# ETH_1G_RGMII_RTL8211F.net
KiCad netlist of a schematic drawn in Altium Designer
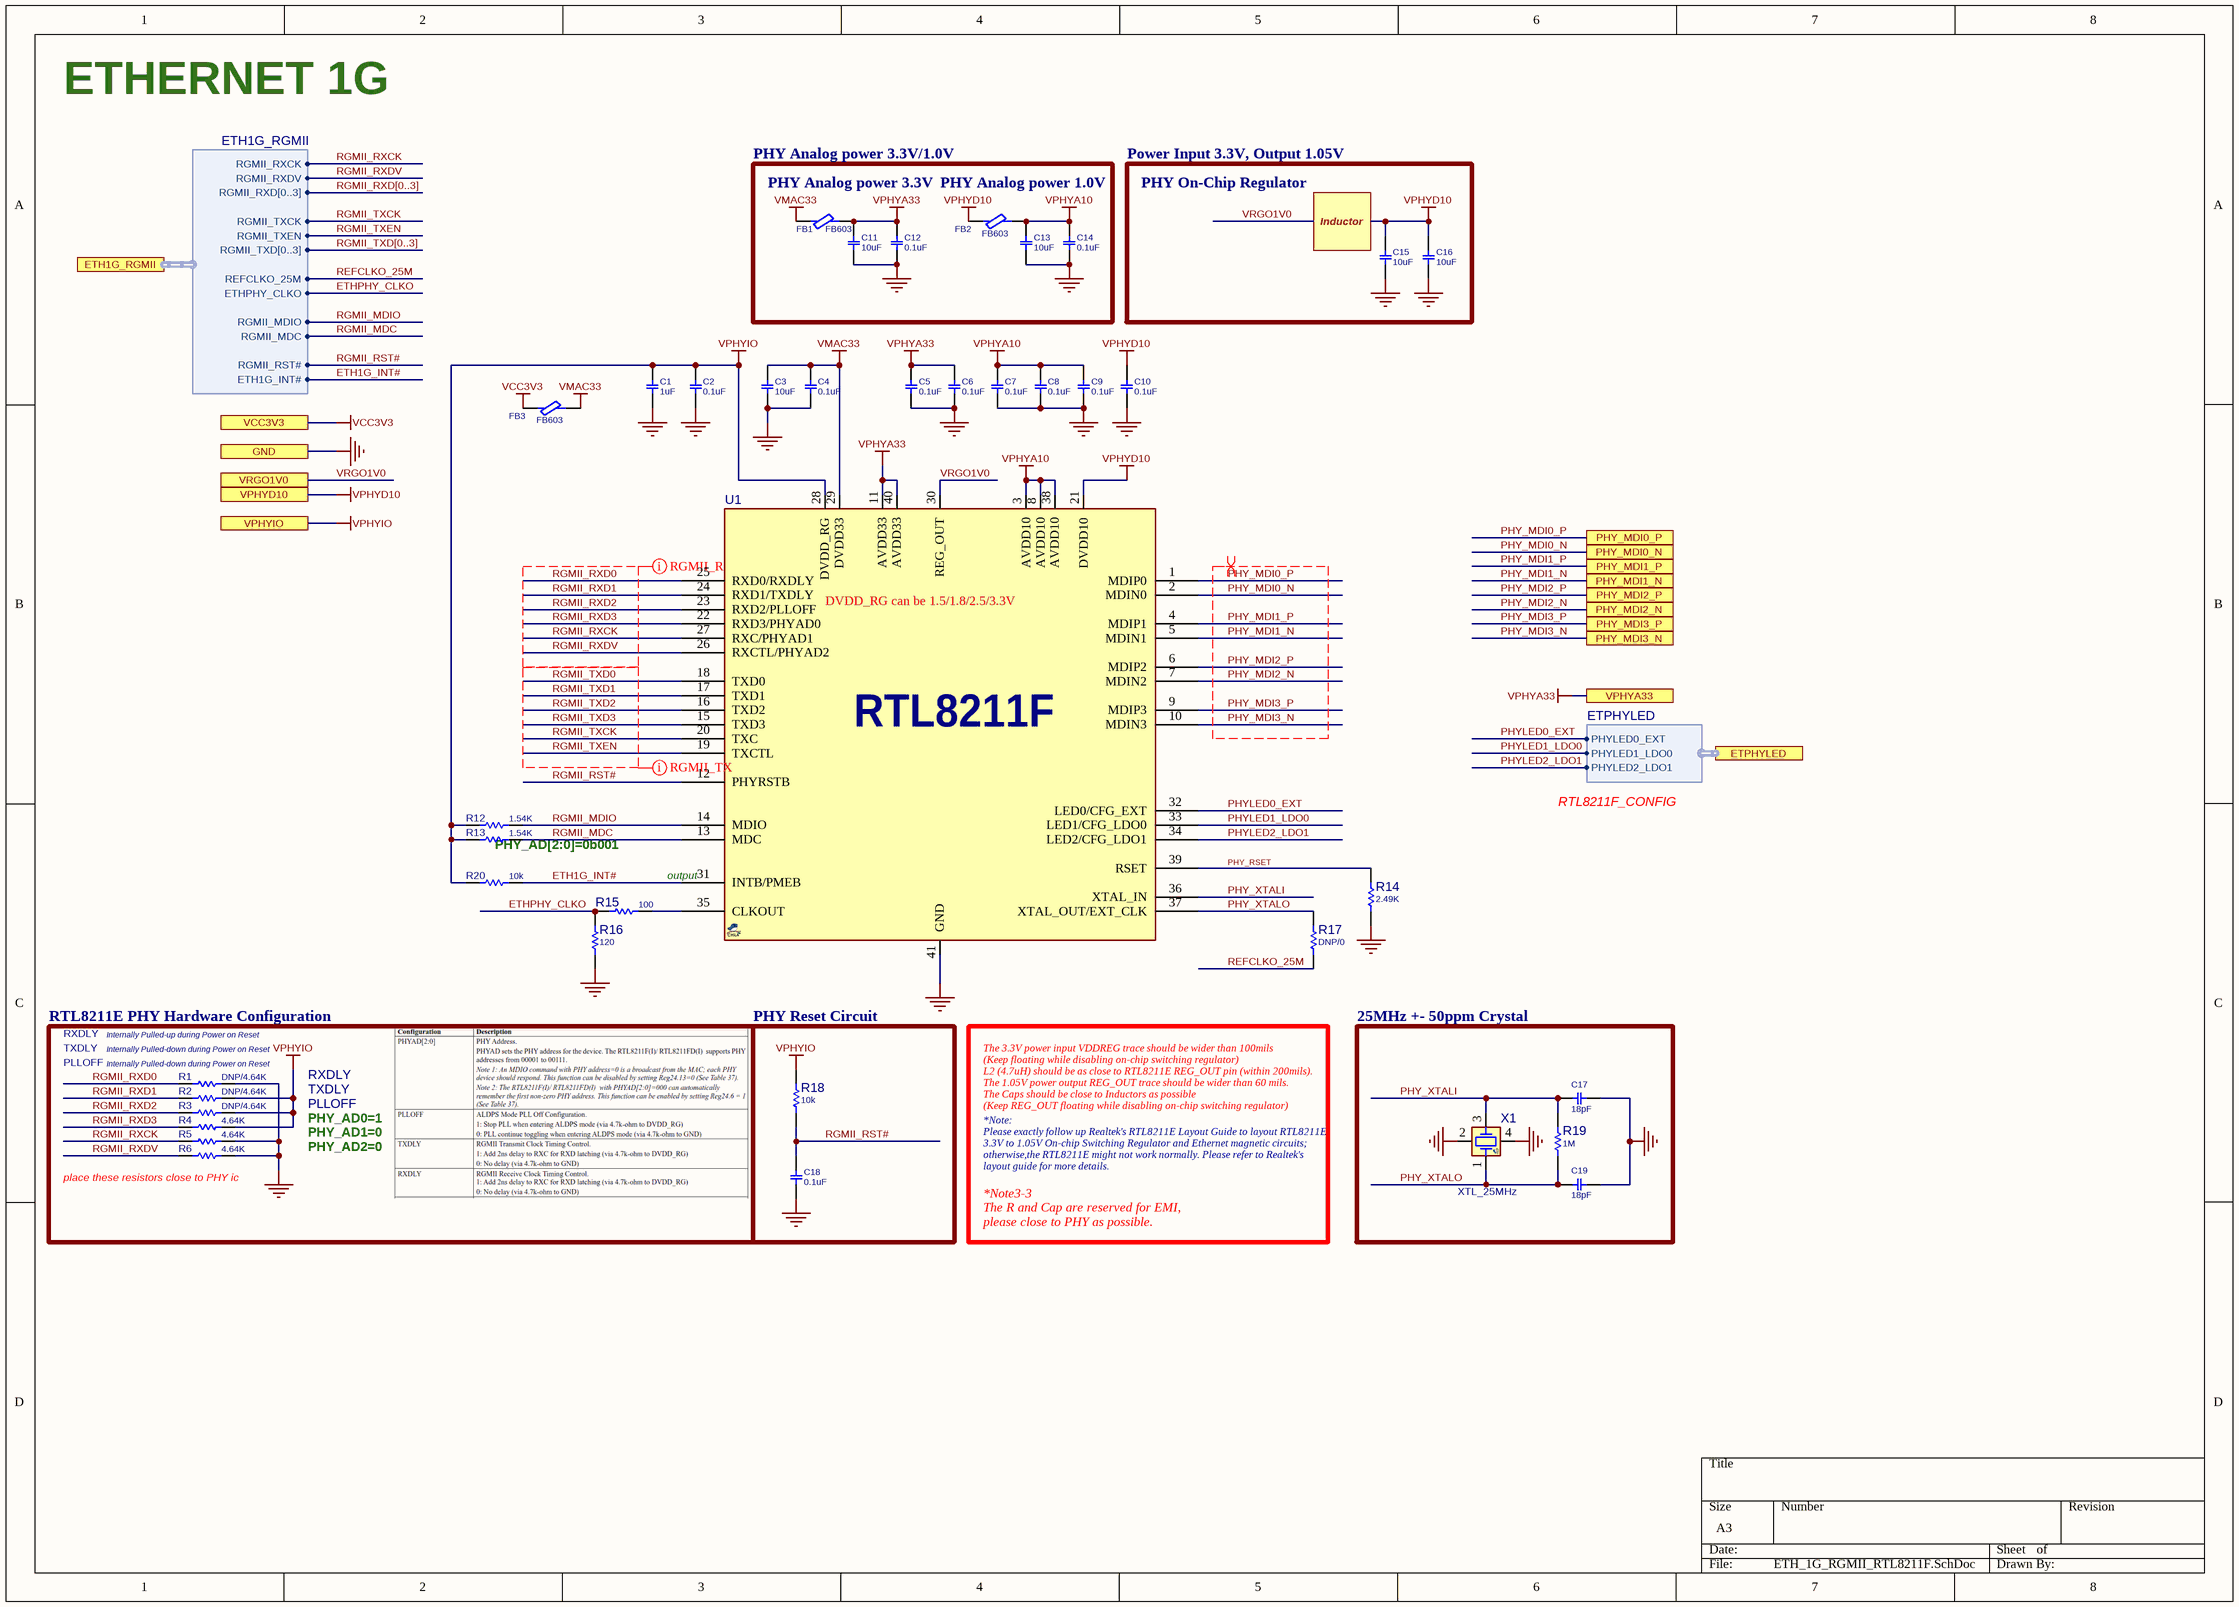
[diagram p0: ETH_1G_RGMII_RTL8211F.SchDoc]

(export (version "E")
  (design (tool "Eeschema 10.0.6"))
  (components
    (comp (ref "C1")
      (value "1uF")
      (footprint "C0402")
      (description "CAP, MLCC")
      (fields (field (name "MANF_P#") "CL05A105KO5NNND") (field (name "MANF") "Samsung"))
      (libsource (lib "passive_smd") (part "CAP_SMD_MLCC"))
    )
    (comp (ref "C2")
      (value "0.1uF")
      (footprint "C0402")
      (description "CAP, MLCC")
      (fields (field (name "MANF_P#") "GRM155R61E104") (field (name "MANF") "Murata"))
      (libsource (lib "mlcc_smd_passive") (part "CAP_SMD_MLCC_100n50T"))
    )
    (comp (ref "C3")
      (value "10uF")
      (footprint "C0402")
      (description "CAP, MLCC")
      (fields (field (name "MANF_P#") "CL05A106MP5NUNC") (field (name "MANF") "Samsung"))
      (libsource (lib "mlcc_smd_passive") (part "CAP_SMD_MLCC_100n50T"))
    )
    (comp (ref "C4")
      (value "0.1uF")
      (footprint "C0402")
      (description "CAP, MLCC")
      (fields (field (name "MANF_P#") "GRM155R61E104") (field (name "MANF") "Murata"))
      (libsource (lib "mlcc_smd_passive") (part "CAP_SMD_MLCC_100n50T"))
    )
    (comp (ref "C5")
      (value "0.1uF")
      (footprint "C0402")
      (description "CAP, MLCC")
      (fields (field (name "MANF_P#") "GRM155R61E104") (field (name "MANF") "Murata"))
      (libsource (lib "mlcc_smd_passive") (part "CAP_SMD_MLCC_100n50T"))
    )
    (comp (ref "C6")
      (value "0.1uF")
      (footprint "C0402")
      (description "CAP, MLCC")
      (fields (field (name "MANF_P#") "GRM155R61E104") (field (name "MANF") "Murata"))
      (libsource (lib "mlcc_smd_passive") (part "CAP_SMD_MLCC_100n50T"))
    )
    (comp (ref "C7")
      (value "0.1uF")
      (footprint "C0402")
      (description "CAP, MLCC")
      (fields (field (name "MANF_P#") "GRM155R61E104") (field (name "MANF") "Murata"))
      (libsource (lib "mlcc_smd_passive") (part "CAP_SMD_MLCC_100n50T"))
    )
    (comp (ref "C8")
      (value "0.1uF")
      (footprint "C0402")
      (description "CAP, MLCC")
      (fields (field (name "MANF_P#") "GRM155R61E104") (field (name "MANF") "Murata"))
      (libsource (lib "mlcc_smd_passive") (part "CAP_SMD_MLCC_100n50T"))
    )
    (comp (ref "C9")
      (value "0.1uF")
      (footprint "C0402")
      (description "CAP, MLCC")
      (fields (field (name "MANF_P#") "GRM155R61E104") (field (name "MANF") "Murata"))
      (libsource (lib "mlcc_smd_passive") (part "CAP_SMD_MLCC_100n50T"))
    )
    (comp (ref "C10")
      (value "0.1uF")
      (footprint "C0402")
      (description "CAP, MLCC")
      (fields (field (name "MANF_P#") "GRM155R61E104") (field (name "MANF") "Murata"))
      (libsource (lib "mlcc_smd_passive") (part "CAP_SMD_MLCC_100n50T"))
    )
    (comp (ref "C11")
      (value "10uF")
      (footprint "C0402")
      (description "CAP, MLCC")
      (fields (field (name "MANF_P#") "CL05A106MP5NUNC") (field (name "MANF") "Samsung"))
      (libsource (lib "mlcc_smd_passive") (part "CAP_SMD_MLCC_100n50T"))
    )
    (comp (ref "C12")
      (value "0.1uF")
      (footprint "C0402")
      (description "CAP, MLCC")
      (fields (field (name "MANF_P#") "GRM155R61E104") (field (name "MANF") "Murata"))
      (libsource (lib "mlcc_smd_passive") (part "CAP_SMD_MLCC_100n50T"))
    )
    (comp (ref "C13")
      (value "10uF")
      (footprint "C0402")
      (description "CAP, MLCC")
      (fields (field (name "MANF_P#") "CL05A106MP5NUNC") (field (name "MANF") "Samsung"))
      (libsource (lib "mlcc_smd_passive") (part "CAP_SMD_MLCC_100n50T"))
    )
    (comp (ref "C14")
      (value "0.1uF")
      (footprint "C0402")
      (description "CAP, MLCC")
      (fields (field (name "MANF_P#") "GRM155R61E104") (field (name "MANF") "Murata"))
      (libsource (lib "mlcc_smd_passive") (part "CAP_SMD_MLCC_100n50T"))
    )
    (comp (ref "C15")
      (value "10uF")
      (footprint "C0402")
      (description "CAP, MLCC")
      (fields (field (name "MANF_P#") "CL05A106MP5NUNC") (field (name "MANF") "Samsung"))
      (libsource (lib "mlcc_smd_passive") (part "CAP_SMD_MLCC_100n50T"))
    )
    (comp (ref "C16")
      (value "10uF")
      (footprint "C0402")
      (description "CAP, MLCC")
      (fields (field (name "MANF_P#") "CL05A106MP5NUNC") (field (name "MANF") "Samsung"))
      (libsource (lib "mlcc_smd_passive") (part "CAP_SMD_MLCC_100n50T"))
    )
    (comp (ref "C17")
      (value "18pF")
      (footprint "C0402")
      (description "CAP, MLCC")
      (fields (field (name "MANF_P#") "CC0402JRNPO9BN180") (field (name "MANF") "Yageo"))
      (libsource (lib "mlcc_smd_passive") (part "CAP_SMD_MLCC_100n50T"))
    )
    (comp (ref "C18")
      (value "0.1uF")
      (footprint "C0402")
      (description "CAP, MLCC")
      (fields (field (name "MANF_P#") "GRM155R61E104") (field (name "MANF") "Murata"))
      (libsource (lib "mlcc_smd_passive") (part "CAP_SMD_MLCC_100n50T"))
    )
    (comp (ref "C19")
      (value "18pF")
      (footprint "C0402")
      (description "CAP, MLCC")
      (fields (field (name "MANF_P#") "CC0402JRNPO9BN180") (field (name "MANF") "Yageo"))
      (libsource (lib "mlcc_smd_passive") (part "CAP_SMD_MLCC_100n50T"))
    )
    (comp (ref "FB1")
      (value "FB603")
      (footprint "L0603")
      (description "FERRITE_Bead, 0603, 0.8A, 300mOhm, 1000@100MHz")
      (fields (field (name "MANF") "MURATA") (field (name "MANF_P#") "BLM18KG601SN1D"))
      (libsource (lib "emi_filter") (part "FBEAD_SMD_MPZ1608S102"))
    )
    (comp (ref "FB2")
      (value "FB603")
      (footprint "L0603")
      (description "FERRITE_Bead, 0603, 0.8A, 300mOhm, 1000@100MHz")
      (fields (field (name "MANF") "MURATA") (field (name "MANF_P#") "BLM18KG601SN1D"))
      (libsource (lib "emi_filter") (part "FBEAD_SMD_MPZ1608S102"))
    )
    (comp (ref "FB3")
      (value "FB603")
      (footprint "L0603")
      (description "FERRITE_Bead, 0603, 0.8A, 300mOhm, 1000@100MHz")
      (fields (field (name "MANF") "MURATA") (field (name "MANF_P#") "BLM18KG601SN1D"))
      (libsource (lib "emi_filter") (part "FBEAD_SMD_MPZ1608S102"))
    )
    (comp (ref "R1")
      (value "DNP/4.64K")
      (footprint "R0402")
      (description "RESISTOR, SMD")
      (libsource (lib "passive_res_smd") (part "RES_SMD_10K_0402"))
    )
    (comp (ref "R2")
      (value "DNP/4.64K")
      (footprint "R0402")
      (description "RESISTOR, SMD")
      (libsource (lib "passive_res_smd") (part "RES_SMD_10K_0402"))
    )
    (comp (ref "R3")
      (value "DNP/4.64K")
      (footprint "R0402")
      (description "RESISTOR, SMD")
      (libsource (lib "passive_res_smd") (part "RES_SMD_10K_0402"))
    )
    (comp (ref "R4")
      (value "4.64K")
      (footprint "R0402")
      (description "RESISTOR, SMD")
      (libsource (lib "passive_res_smd") (part "RES_SMD_10K_0402"))
    )
    (comp (ref "R5")
      (value "4.64K")
      (footprint "R0402")
      (description "RESISTOR, SMD")
      (libsource (lib "passive_res_smd") (part "RES_SMD_10K_0402"))
    )
    (comp (ref "R6")
      (value "4.64K")
      (footprint "R0402")
      (description "RESISTOR, SMD")
      (libsource (lib "passive_res_smd") (part "RES_SMD_10K_0402"))
    )
    (comp (ref "R12")
      (value "1.54K")
      (footprint "R0402")
      (description "RESISTOR, SMD")
      (libsource (lib "passive_res_smd") (part "RES_SMD_10K_0402"))
    )
    (comp (ref "R13")
      (value "1.54K")
      (footprint "R0402")
      (description "RESISTOR, SMD")
      (libsource (lib "passive_res_smd") (part "RES_SMD_10K_0402"))
    )
    (comp (ref "R14")
      (value "2.49K")
      (footprint "R0402")
      (description "RESISTOR, SMD")
      (libsource (lib "passive_res_smd") (part "RES_SMD_10K_0402"))
    )
    (comp (ref "R15")
      (value "100")
      (footprint "R0402")
      (description "RESISTOR, SMD")
      (libsource (lib "passive_res_smd") (part "RES_SMD_10K_0402"))
    )
    (comp (ref "R16")
      (value "120")
      (footprint "R0402")
      (description "RESISTOR, SMD")
      (libsource (lib "passive_res_smd") (part "RES_SMD_10K_0402"))
    )
    (comp (ref "R17")
      (value "DNP/0")
      (footprint "R0402")
      (description "RESISTOR, SMD")
      (libsource (lib "passive_res_smd") (part "RES_SMD_10K_0402"))
    )
    (comp (ref "R18")
      (value "10k")
      (footprint "R0402")
      (description "RESISTOR, SMD")
      (libsource (lib "passive_res_smd") (part "RES_SMD_10K_0402"))
    )
    (comp (ref "R19")
      (value "1M")
      (footprint "R0402")
      (description "RESISTOR, SMD")
      (libsource (lib "passive_res_smd") (part "RES_SMD_10K_0402"))
    )
    (comp (ref "R20")
      (value "10k")
      (footprint "R0402")
      (description "RESISTOR, SMD")
      (libsource (lib "passive_res_smd") (part "RES_SMD_10K_0402"))
    )
    (comp (ref "U1")
      (value "RTL8211F")
      (footprint "QFN40_40T")
      (description "Ethernet Transceiver, 10/100/1000, RGMII")
      (fields (field (name "MANF_P#") "RTL8211FI-CG") (field (name "MANF") "Realtek"))
      (libsource (lib "ethernet") (part "RTL8211F_QFN40"))
    )
    (comp (ref "X1")
      (value "XTL_25MHz")
      (footprint "XTL_4_2016")
      (description "CRYSTAL 25.00 MHZ 6pF, 10PPM")
      (fields (field (name "MANF") "Murata") (field (name "MANF_P#") "XRCGB25M000F1H00R0"))
      (libsource (lib "crystal") (part "XTL_4_25MHz_3225"))
    )
  )
  (nets
    (net (code "3") (name "/ETH1G_INT#") (class "Default")
      (node (ref "R20") (pin "2") (pinfunction "2_2") (pintype "passive"))
      (node (ref "U1") (pin "31") (pinfunction "INTB/PMEB_31") (pintype "passive"))
    )
    (net (code "4") (name "/ETHPHY_CLKO") (class "Default")
      (node (ref "R15") (pin "1") (pinfunction "1_1") (pintype "passive"))
      (node (ref "R16") (pin "2") (pinfunction "2_2") (pintype "passive"))
    )
    (net (code "5") (name "/PHYLED0_EXT") (class "Default")
      (node (ref "U1") (pin "32") (pinfunction "LED0/CFG_EXT_32") (pintype "passive"))
    )
    (net (code "6") (name "/PHYLED1_LDO0") (class "Default")
      (node (ref "U1") (pin "33") (pinfunction "LED1/CFG_LDO0_33") (pintype "passive"))
    )
    (net (code "7") (name "/PHYLED2_LDO1") (class "Default")
      (node (ref "U1") (pin "34") (pinfunction "LED2/CFG_LDO1_34") (pintype "passive"))
    )
    (net (code "8") (name "/PHY_MDI0_N") (class "Default")
      (node (ref "U1") (pin "2") (pinfunction "MDIN0_2") (pintype "passive"))
    )
    (net (code "9") (name "/PHY_MDI0_P") (class "Default")
      (node (ref "U1") (pin "1") (pinfunction "MDIP0_1") (pintype "passive"))
    )
    (net (code "10") (name "/PHY_MDI1_N") (class "Default")
      (node (ref "U1") (pin "5") (pinfunction "MDIN1_5") (pintype "passive"))
    )
    (net (code "11") (name "/PHY_MDI1_P") (class "Default")
      (node (ref "U1") (pin "4") (pinfunction "MDIP1_4") (pintype "passive"))
    )
    (net (code "12") (name "/PHY_MDI2_N") (class "Default")
      (node (ref "U1") (pin "7") (pinfunction "MDIN2_7") (pintype "passive"))
    )
    (net (code "13") (name "/PHY_MDI2_P") (class "Default")
      (node (ref "U1") (pin "6") (pinfunction "MDIP2_6") (pintype "passive"))
    )
    (net (code "14") (name "/PHY_MDI3_N") (class "Default")
      (node (ref "U1") (pin "10") (pinfunction "MDIN3_10") (pintype "passive"))
    )
    (net (code "15") (name "/PHY_MDI3_P") (class "Default")
      (node (ref "U1") (pin "9") (pinfunction "MDIP3_9") (pintype "passive"))
    )
    (net (code "16") (name "/PHY_RSET") (class "Default")
      (node (ref "R14") (pin "2") (pinfunction "2_2") (pintype "passive"))
      (node (ref "U1") (pin "39") (pinfunction "RSET_39") (pintype "passive"))
    )
    (net (code "17") (name "/PHY_XTALI") (class "Default")
      (node (ref "C17") (pin "1") (pinfunction "1_1") (pintype "passive"))
      (node (ref "R19") (pin "2") (pinfunction "2_2") (pintype "passive"))
      (node (ref "U1") (pin "36") (pinfunction "XTAL_IN_36") (pintype "passive"))
      (node (ref "X1") (pin "3") (pinfunction "XB_3") (pintype "passive"))
    )
    (net (code "18") (name "/PHY_XTALO") (class "Default")
      (node (ref "C19") (pin "1") (pinfunction "1_1") (pintype "passive"))
      (node (ref "R17") (pin "2") (pinfunction "2_2") (pintype "passive"))
      (node (ref "R19") (pin "1") (pinfunction "1_1") (pintype "passive"))
      (node (ref "U1") (pin "37") (pinfunction "XTAL_OUT/EXT_CLK_37") (pintype "passive"))
      (node (ref "X1") (pin "1") (pinfunction "XA_1") (pintype "passive"))
    )
    (net (code "19") (name "/REFCLKO_25M") (class "Default")
      (node (ref "R17") (pin "1") (pinfunction "1_1") (pintype "passive"))
    )
    (net (code "20") (name "/RGMII_MDC") (class "Default")
      (node (ref "R13") (pin "2") (pinfunction "2_2") (pintype "passive"))
      (node (ref "U1") (pin "13") (pinfunction "MDC_13") (pintype "passive"))
    )
    (net (code "21") (name "/RGMII_MDIO") (class "Default")
      (node (ref "R12") (pin "2") (pinfunction "2_2") (pintype "passive"))
      (node (ref "U1") (pin "14") (pinfunction "MDIO_14") (pintype "passive"))
    )
    (net (code "22") (name "/RGMII_RST#") (class "Default")
      (node (ref "C18") (pin "2") (pinfunction "2_2") (pintype "passive"))
      (node (ref "R18") (pin "2") (pinfunction "2_2") (pintype "passive"))
      (node (ref "U1") (pin "12") (pinfunction "PHYRSTB_12") (pintype "passive"))
    )
    (net (code "23") (name "/RGMII_RXCK") (class "Default")
      (node (ref "R5") (pin "1") (pinfunction "1_1") (pintype "passive"))
      (node (ref "U1") (pin "27") (pinfunction "RXC/PHYAD1_27") (pintype "passive"))
    )
    (net (code "24") (name "/RGMII_RXD0") (class "Default")
      (node (ref "R1") (pin "1") (pinfunction "1_1") (pintype "passive"))
      (node (ref "U1") (pin "25") (pinfunction "RXD0/RXDLY_25") (pintype "passive"))
    )
    (net (code "25") (name "/RGMII_RXD1") (class "Default")
      (node (ref "R2") (pin "1") (pinfunction "1_1") (pintype "passive"))
      (node (ref "U1") (pin "24") (pinfunction "RXD1/TXDLY_24") (pintype "passive"))
    )
    (net (code "26") (name "/RGMII_RXD2") (class "Default")
      (node (ref "R3") (pin "1") (pinfunction "1_1") (pintype "passive"))
      (node (ref "U1") (pin "23") (pinfunction "RXD2/PLLOFF_23") (pintype "passive"))
    )
    (net (code "27") (name "/RGMII_RXD3") (class "Default")
      (node (ref "R4") (pin "1") (pinfunction "1_1") (pintype "passive"))
      (node (ref "U1") (pin "22") (pinfunction "RXD3/PHYAD0_22") (pintype "passive"))
    )
    (net (code "28") (name "/RGMII_RXDV") (class "Default")
      (node (ref "R6") (pin "1") (pinfunction "1_1") (pintype "passive"))
      (node (ref "U1") (pin "26") (pinfunction "RXCTL/PHYAD2_26") (pintype "passive"))
    )
    (net (code "30") (name "/RGMII_TXCK") (class "Default")
      (node (ref "U1") (pin "20") (pinfunction "TXC_20") (pintype "passive"))
    )
    (net (code "31") (name "/RGMII_TXD0") (class "Default")
      (node (ref "U1") (pin "18") (pinfunction "TXD0_18") (pintype "passive"))
    )
    (net (code "32") (name "/RGMII_TXD1") (class "Default")
      (node (ref "U1") (pin "17") (pinfunction "TXD1_17") (pintype "passive"))
    )
    (net (code "33") (name "/RGMII_TXD2") (class "Default")
      (node (ref "U1") (pin "16") (pinfunction "TXD2_16") (pintype "passive"))
    )
    (net (code "34") (name "/RGMII_TXD3") (class "Default")
      (node (ref "U1") (pin "15") (pinfunction "TXD3_15") (pintype "passive"))
    )
    (net (code "36") (name "/RGMII_TXEN") (class "Default")
      (node (ref "U1") (pin "19") (pinfunction "TXCTL_19") (pintype "passive"))
    )
    (net (code "37") (name "/VRGO1V0") (class "Default")
      (node (ref "U1") (pin "30") (pinfunction "REG_OUT_30") (pintype "passive"))
    )
    (net (code "40") (name "GND") (class "Default")
      (node (ref "C1") (pin "1") (pinfunction "1_1") (pintype "passive"))
      (node (ref "C10") (pin "2") (pinfunction "2_2") (pintype "passive"))
      (node (ref "C11") (pin "2") (pinfunction "2_2") (pintype "passive"))
      (node (ref "C12") (pin "2") (pinfunction "2_2") (pintype "passive"))
      (node (ref "C13") (pin "2") (pinfunction "2_2") (pintype "passive"))
      (node (ref "C14") (pin "2") (pinfunction "2_2") (pintype "passive"))
      (node (ref "C15") (pin "2") (pinfunction "2_2") (pintype "passive"))
      (node (ref "C16") (pin "2") (pinfunction "2_2") (pintype "passive"))
      (node (ref "C17") (pin "2") (pinfunction "2_2") (pintype "passive"))
      (node (ref "C18") (pin "1") (pinfunction "1_1") (pintype "passive"))
      (node (ref "C19") (pin "2") (pinfunction "2_2") (pintype "passive"))
      (node (ref "C2") (pin "2") (pinfunction "2_2") (pintype "passive"))
      (node (ref "C3") (pin "2") (pinfunction "2_2") (pintype "passive"))
      (node (ref "C4") (pin "2") (pinfunction "2_2") (pintype "passive"))
      (node (ref "C5") (pin "2") (pinfunction "2_2") (pintype "passive"))
      (node (ref "C6") (pin "2") (pinfunction "2_2") (pintype "passive"))
      (node (ref "C7") (pin "2") (pinfunction "2_2") (pintype "passive"))
      (node (ref "C8") (pin "2") (pinfunction "2_2") (pintype "passive"))
      (node (ref "C9") (pin "2") (pinfunction "2_2") (pintype "passive"))
      (node (ref "R1") (pin "2") (pinfunction "2_2") (pintype "passive"))
      (node (ref "R14") (pin "1") (pinfunction "1_1") (pintype "passive"))
      (node (ref "R16") (pin "1") (pinfunction "1_1") (pintype "passive"))
      (node (ref "R5") (pin "2") (pinfunction "2_2") (pintype "passive"))
      (node (ref "R6") (pin "2") (pinfunction "2_2") (pintype "passive"))
      (node (ref "U1") (pin "41") (pinfunction "GND_41") (pintype "passive"))
      (node (ref "X1") (pin "2") (pinfunction "GND1_2") (pintype "passive"))
      (node (ref "X1") (pin "4") (pinfunction "GND2_4") (pintype "passive"))
    )
    (net (code "41") (name "Net-(U1-CLKOUT)") (class "Default")
      (node (ref "R15") (pin "2") (pinfunction "2_2") (pintype "passive"))
      (node (ref "U1") (pin "35") (pinfunction "CLKOUT_35") (pintype "passive"))
    )
    (net (code "42") (name "VCC3V3") (class "Default")
      (node (ref "FB3") (pin "1") (pinfunction "1_1") (pintype "passive"))
    )
    (net (code "43") (name "VMAC33") (class "Default")
      (node (ref "C3") (pin "1") (pinfunction "1_1") (pintype "passive"))
      (node (ref "C4") (pin "1") (pinfunction "1_1") (pintype "passive"))
      (node (ref "FB1") (pin "1") (pinfunction "1_1") (pintype "passive"))
      (node (ref "FB3") (pin "2") (pinfunction "2_2") (pintype "passive"))
      (node (ref "U1") (pin "29") (pinfunction "DVDD33_29") (pintype "passive"))
    )
    (net (code "44") (name "VPHYA10") (class "Default")
      (node (ref "C13") (pin "1") (pinfunction "1_1") (pintype "passive"))
      (node (ref "C14") (pin "1") (pinfunction "1_1") (pintype "passive"))
      (node (ref "C7") (pin "1") (pinfunction "1_1") (pintype "passive"))
      (node (ref "C8") (pin "1") (pinfunction "1_1") (pintype "passive"))
      (node (ref "C9") (pin "1") (pinfunction "1_1") (pintype "passive"))
      (node (ref "FB2") (pin "2") (pinfunction "2_2") (pintype "passive"))
      (node (ref "U1") (pin "3") (pinfunction "AVDD10_3") (pintype "passive"))
      (node (ref "U1") (pin "38") (pinfunction "AVDD10_38") (pintype "passive"))
      (node (ref "U1") (pin "8") (pinfunction "AVDD10_8") (pintype "passive"))
    )
    (net (code "45") (name "VPHYA33") (class "Default")
      (node (ref "C11") (pin "1") (pinfunction "1_1") (pintype "passive"))
      (node (ref "C12") (pin "1") (pinfunction "1_1") (pintype "passive"))
      (node (ref "C5") (pin "1") (pinfunction "1_1") (pintype "passive"))
      (node (ref "C6") (pin "1") (pinfunction "1_1") (pintype "passive"))
      (node (ref "FB1") (pin "2") (pinfunction "2_2") (pintype "passive"))
      (node (ref "U1") (pin "11") (pinfunction "AVDD33_11") (pintype "passive"))
      (node (ref "U1") (pin "40") (pinfunction "AVDD33_40") (pintype "passive"))
    )
    (net (code "46") (name "VPHYD10") (class "Default")
      (node (ref "C10") (pin "1") (pinfunction "1_1") (pintype "passive"))
      (node (ref "C15") (pin "1") (pinfunction "1_1") (pintype "passive"))
      (node (ref "C16") (pin "1") (pinfunction "1_1") (pintype "passive"))
      (node (ref "FB2") (pin "1") (pinfunction "1_1") (pintype "passive"))
      (node (ref "U1") (pin "21") (pinfunction "DVDD10_21") (pintype "passive"))
    )
    (net (code "47") (name "VPHYIO") (class "Default")
      (node (ref "C1") (pin "2") (pinfunction "2_2") (pintype "passive"))
      (node (ref "C2") (pin "1") (pinfunction "1_1") (pintype "passive"))
      (node (ref "R12") (pin "1") (pinfunction "1_1") (pintype "passive"))
      (node (ref "R13") (pin "1") (pinfunction "1_1") (pintype "passive"))
      (node (ref "R18") (pin "1") (pinfunction "1_1") (pintype "passive"))
      (node (ref "R2") (pin "2") (pinfunction "2_2") (pintype "passive"))
      (node (ref "R20") (pin "1") (pinfunction "1_1") (pintype "passive"))
      (node (ref "R3") (pin "2") (pinfunction "2_2") (pintype "passive"))
      (node (ref "R4") (pin "2") (pinfunction "2_2") (pintype "passive"))
      (node (ref "U1") (pin "28") (pinfunction "DVDD_RG_28") (pintype "passive"))
    )
  )
)
